# bpf-L-band-BPF-F1250.net
KiCad netlist of a schematic drawn in EAGLE
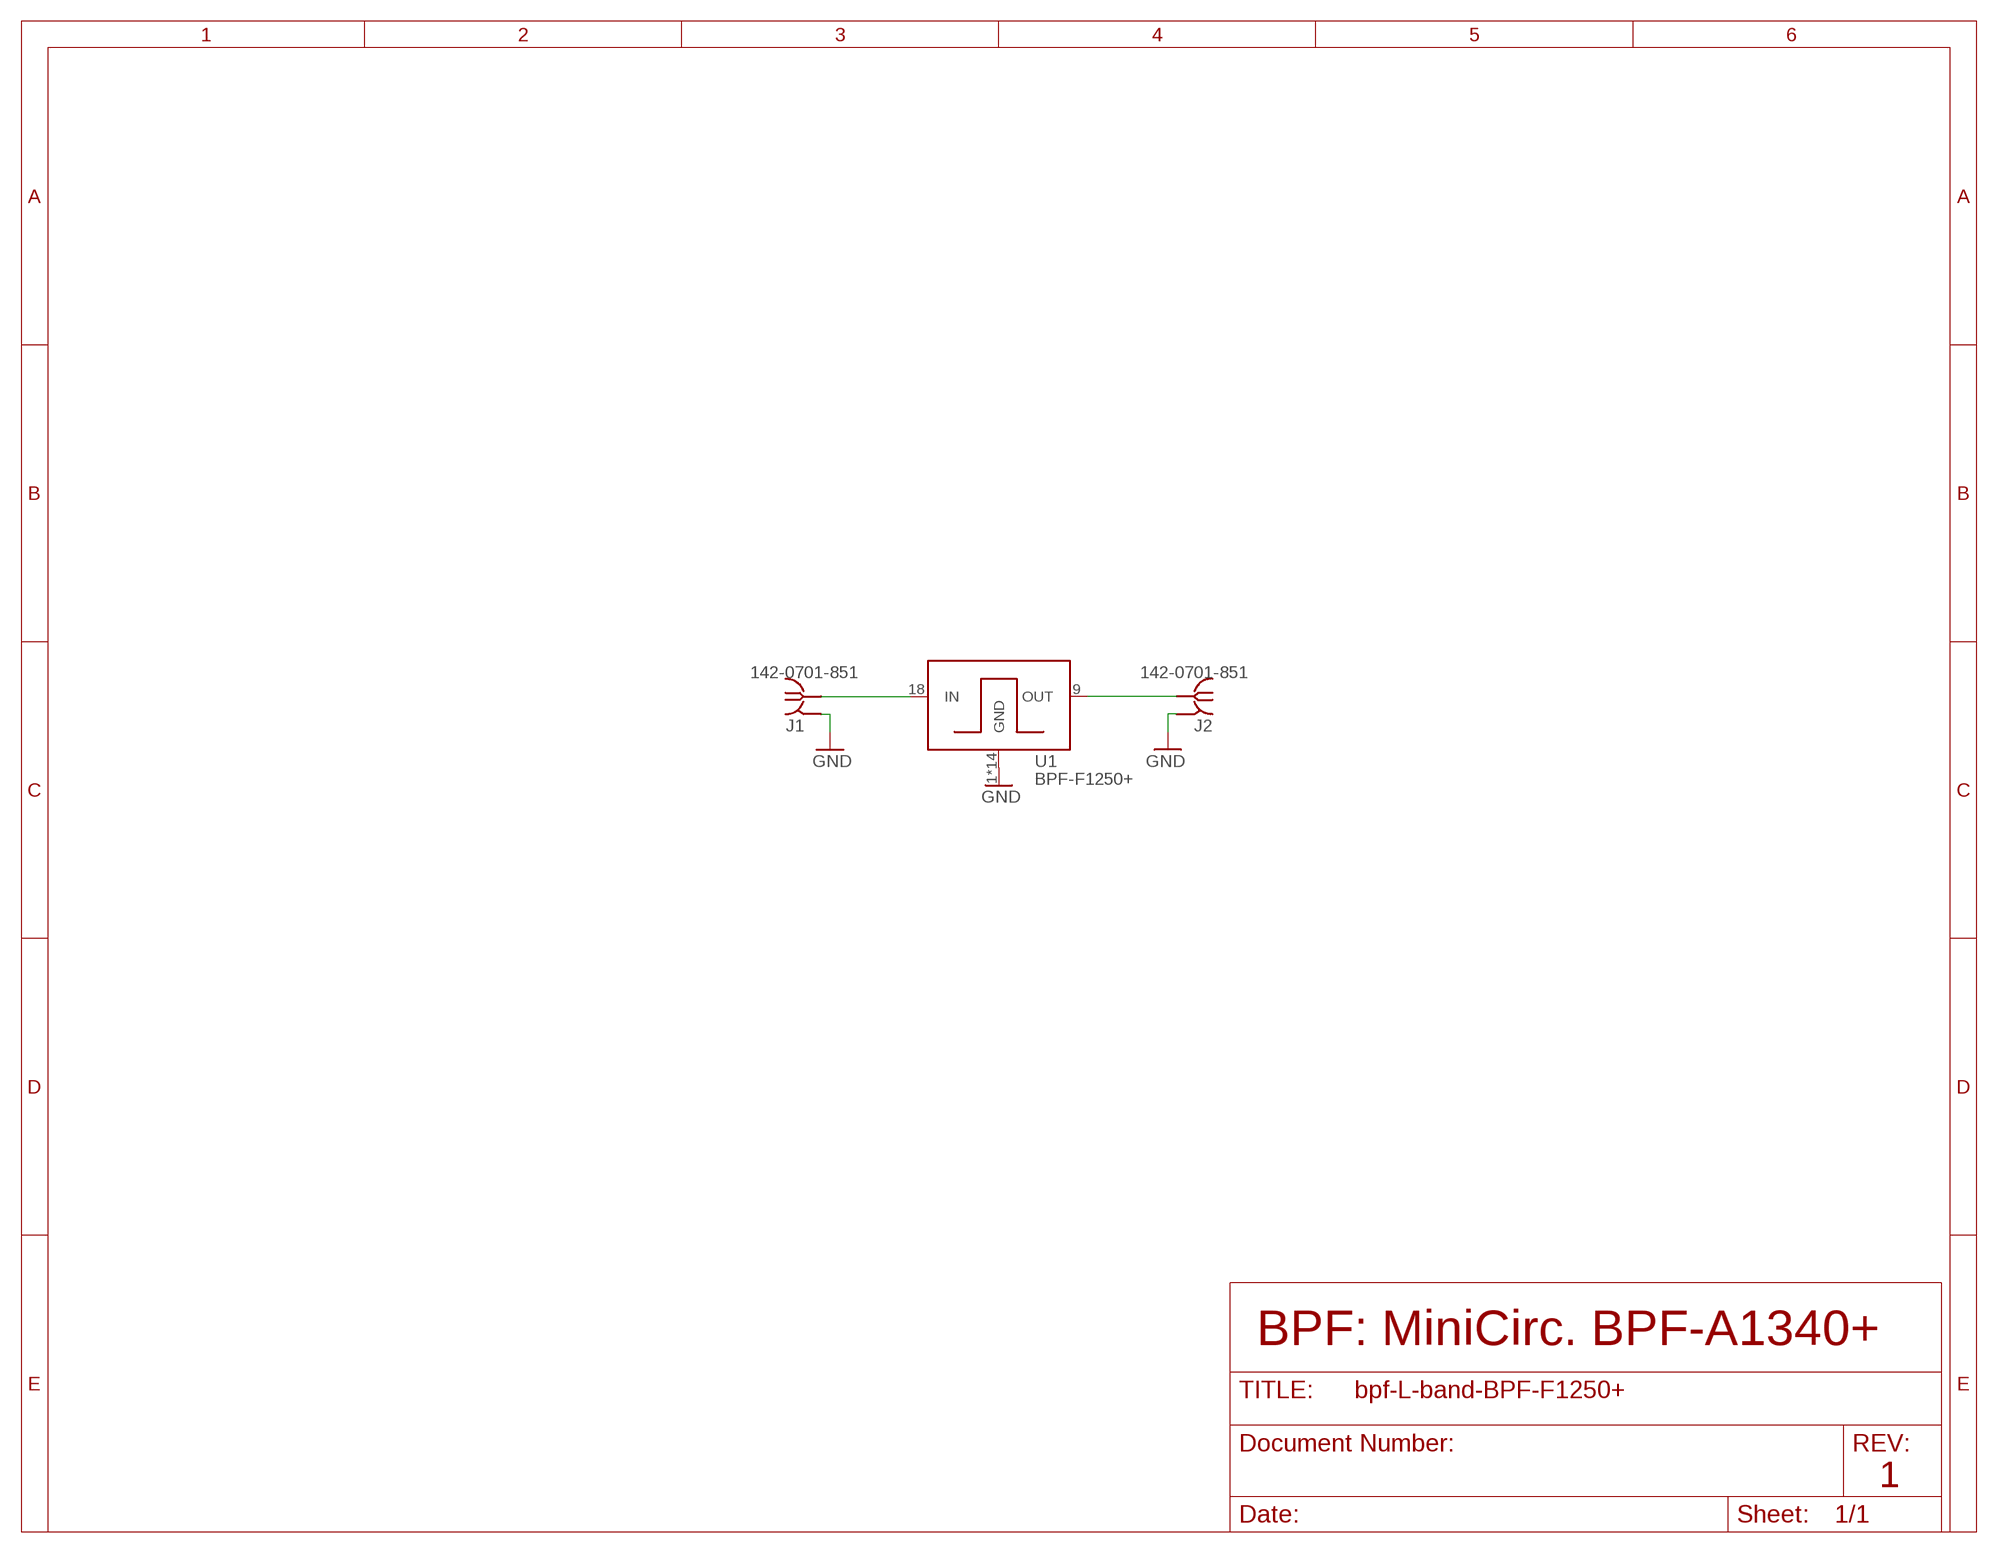
[diagram p0: schematic, sheet 1]

(export (version "E")
  (design (tool "Eeschema 10.0.6"))
  (components
    (comp (ref "J1")
      (value "142-0701-851")
      (footprint "eagle-import:142-0701-851")
      (libsource (lib "eagle-import") (part "142-0701-851"))
    )
    (comp (ref "J2")
      (value "142-0701-851")
      (footprint "eagle-import:142-0701-851")
      (libsource (lib "eagle-import") (part "142-0701-851"))
    )
    (comp (ref "U1")
      (value "BPF-F1250+")
      (footprint "eagle-import:BPF-F1250+")
      (libsource (lib "eagle-import") (part "BPF-F1250+"))
    )
  )
  (nets
    (net (code "1") (name "GND") (class "Default")
      (node (ref "J1") (pin "GND1") (pinfunction "GND_GND1") (pintype "bidirectional"))
      (node (ref "J1") (pin "GND2") (pinfunction "GND_GND2") (pintype "bidirectional"))
      (node (ref "J1") (pin "GND3") (pinfunction "GND_GND3") (pintype "bidirectional"))
      (node (ref "J1") (pin "GND4") (pinfunction "GND_GND4") (pintype "bidirectional"))
      (node (ref "J2") (pin "GND1") (pinfunction "GND_GND1") (pintype "bidirectional"))
      (node (ref "J2") (pin "GND2") (pinfunction "GND_GND2") (pintype "bidirectional"))
      (node (ref "J2") (pin "GND3") (pinfunction "GND_GND3") (pintype "bidirectional"))
      (node (ref "J2") (pin "GND4") (pinfunction "GND_GND4") (pintype "bidirectional"))
      (node (ref "U1") (pin "1") (pinfunction "GND_1") (pintype "power_in"))
      (node (ref "U1") (pin "10") (pinfunction "GND_10") (pintype "power_in"))
      (node (ref "U1") (pin "12") (pinfunction "GND_12") (pintype "power_in"))
      (node (ref "U1") (pin "13") (pinfunction "GND_13") (pintype "power_in"))
      (node (ref "U1") (pin "14") (pinfunction "GND_14") (pintype "power_in"))
      (node (ref "U1") (pin "15") (pinfunction "GND_15") (pintype "power_in"))
      (node (ref "U1") (pin "16") (pinfunction "GND_16") (pintype "power_in"))
      (node (ref "U1") (pin "17") (pinfunction "GND_17") (pintype "power_in"))
      (node (ref "U1") (pin "3") (pinfunction "GND_3") (pintype "power_in"))
      (node (ref "U1") (pin "4") (pinfunction "GND_4") (pintype "power_in"))
      (node (ref "U1") (pin "5") (pinfunction "GND_5") (pintype "power_in"))
      (node (ref "U1") (pin "6") (pinfunction "GND_6") (pintype "power_in"))
      (node (ref "U1") (pin "7") (pinfunction "GND_7") (pintype "power_in"))
      (node (ref "U1") (pin "8") (pinfunction "GND_8") (pintype "power_in"))
    )
    (net (code "2") (name "Net-(J1-RF)") (class "Default")
      (node (ref "J1") (pin "RF1") (pinfunction "RF_RF1") (pintype "bidirectional"))
      (node (ref "U1") (pin "18") (pinfunction "IN_18") (pintype "input"))
    )
    (net (code "3") (name "Net-(J2-RF)") (class "Default")
      (node (ref "J2") (pin "RF1") (pinfunction "RF_RF1") (pintype "bidirectional"))
      (node (ref "U1") (pin "9") (pinfunction "OUT_9") (pintype "output"))
    )
  )
)
